# reversed.net
KiCad netlist of a schematic drawn in EAGLE
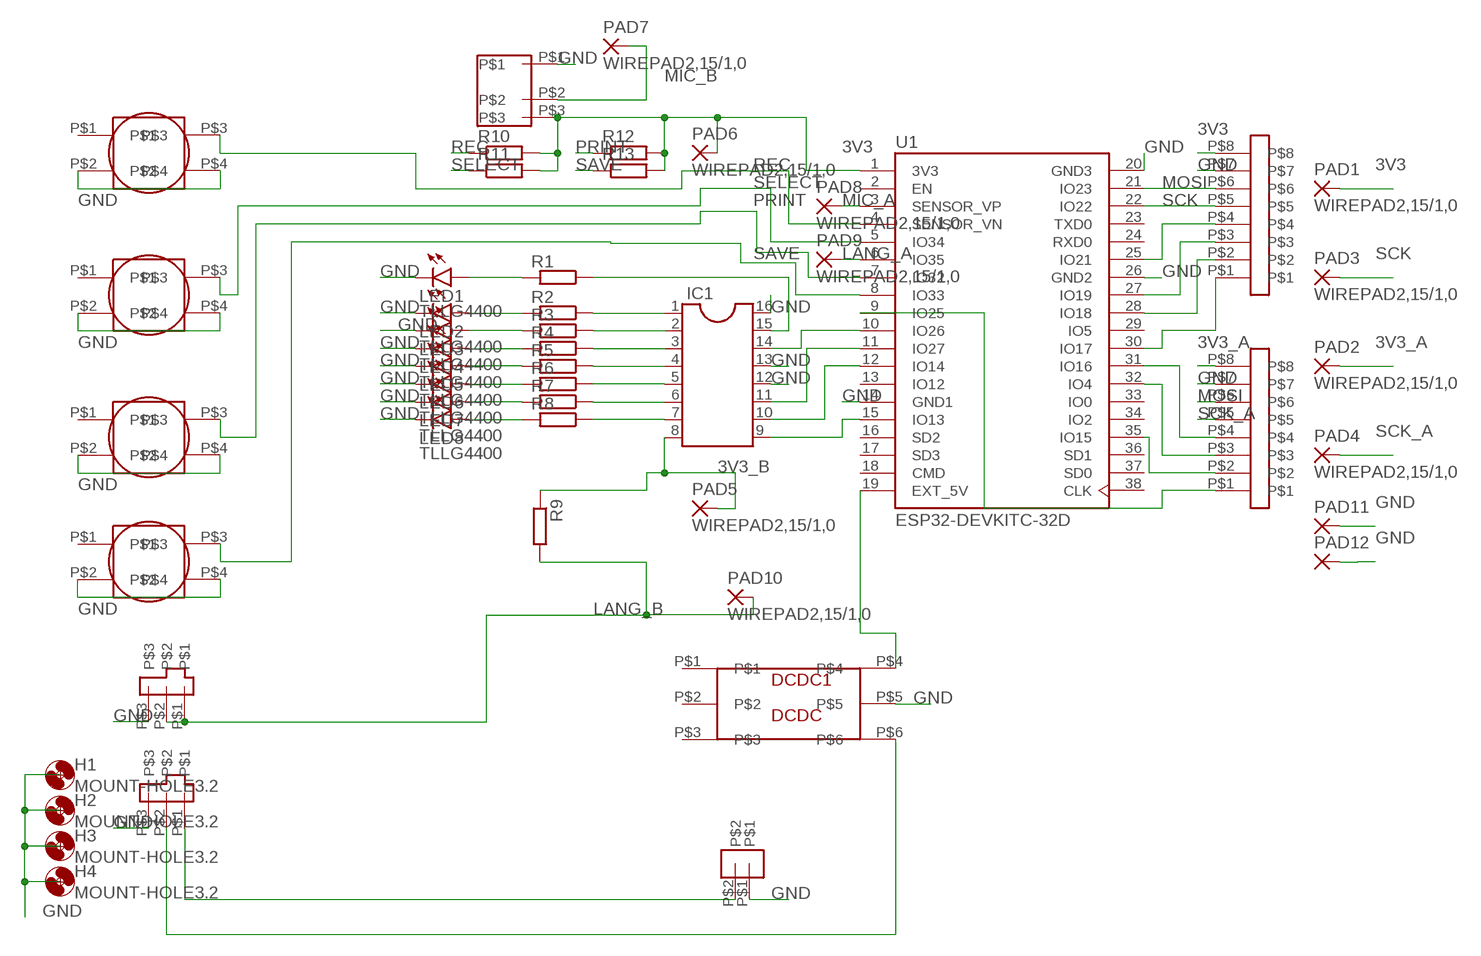
[diagram p0: schematic, sheet 1]

(export (version "E")
  (design (tool "Eeschema 10.0.6"))
  (components
    (comp (ref "BATTERY1")
      (value "BATTERY")
      (footprint "eagle-import:BATTERY")
      (libsource (lib "eagle-import") (part "BATTERY"))
    )
    (comp (ref "DCDC1")
      (value "DCDC")
      (footprint "eagle-import:DCDC")
      (libsource (lib "eagle-import") (part "DCDC"))
    )
    (comp (ref "DISPLAY1")
      (value "DISPLAY")
      (footprint "eagle-import:DISPLAY")
      (libsource (lib "eagle-import") (part "DISPLAY"))
    )
    (comp (ref "DISPLAY2")
      (value "DISPLAY")
      (footprint "eagle-import:DISPLAY")
      (libsource (lib "eagle-import") (part "DISPLAY"))
    )
    (comp (ref "H1")
      (value "MOUNT-HOLE3.2")
      (footprint "eagle-import:3,2")
      (libsource (lib "eagle-import") (part "MOUNT-HOLE3.2"))
    )
    (comp (ref "H2")
      (value "MOUNT-HOLE3.2")
      (footprint "eagle-import:3,2")
      (libsource (lib "eagle-import") (part "MOUNT-HOLE3.2"))
    )
    (comp (ref "H3")
      (value "MOUNT-HOLE3.2")
      (footprint "eagle-import:3,2")
      (libsource (lib "eagle-import") (part "MOUNT-HOLE3.2"))
    )
    (comp (ref "H4")
      (value "MOUNT-HOLE3.2")
      (footprint "eagle-import:3,2")
      (libsource (lib "eagle-import") (part "MOUNT-HOLE3.2"))
    )
    (comp (ref "IC1")
      (value "DIL16S")
      (footprint "eagle-import:SOCKET-16")
      (libsource (lib "eagle-import") (part "DIL16S"))
    )
    (comp (ref "LED1")
      (value "TLLG4400")
      (footprint "eagle-import:LED3MM")
      (fields (field (name "MF") "VISHAY SEMICONDUCTOR"))
      (libsource (lib "eagle-import") (part "TLLG4400"))
    )
    (comp (ref "LED2")
      (value "TLLG4400")
      (footprint "eagle-import:LED3MM")
      (fields (field (name "MF") "VISHAY SEMICONDUCTOR"))
      (libsource (lib "eagle-import") (part "TLLG4400"))
    )
    (comp (ref "LED3")
      (value "TLLG4400")
      (footprint "eagle-import:LED3MM")
      (fields (field (name "MF") "VISHAY SEMICONDUCTOR"))
      (libsource (lib "eagle-import") (part "TLLG4400"))
    )
    (comp (ref "LED4")
      (value "TLLG4400")
      (footprint "eagle-import:LED3MM")
      (fields (field (name "MF") "VISHAY SEMICONDUCTOR"))
      (libsource (lib "eagle-import") (part "TLLG4400"))
    )
    (comp (ref "LED5")
      (value "TLLG4400")
      (footprint "eagle-import:LED3MM")
      (fields (field (name "MF") "VISHAY SEMICONDUCTOR"))
      (libsource (lib "eagle-import") (part "TLLG4400"))
    )
    (comp (ref "LED6")
      (value "TLLG4400")
      (footprint "eagle-import:LED3MM")
      (fields (field (name "MF") "VISHAY SEMICONDUCTOR"))
      (libsource (lib "eagle-import") (part "TLLG4400"))
    )
    (comp (ref "LED7")
      (value "TLLG4400")
      (footprint "eagle-import:LED3MM")
      (fields (field (name "MF") "VISHAY SEMICONDUCTOR"))
      (libsource (lib "eagle-import") (part "TLLG4400"))
    )
    (comp (ref "LED8")
      (value "TLLG4400")
      (footprint "eagle-import:LED3MM")
      (fields (field (name "MF") "VISHAY SEMICONDUCTOR"))
      (libsource (lib "eagle-import") (part "TLLG4400"))
    )
    (comp (ref "MIC1")
      (value "MIC")
      (footprint "eagle-import:MIC")
      (libsource (lib "eagle-import") (part "MIC"))
    )
    (comp (ref "PAD1")
      (value "WIREPAD2,15/1,0")
      (footprint "eagle-import:2,15_1,0")
      (libsource (lib "eagle-import") (part "WIREPAD2,15/1,0"))
    )
    (comp (ref "PAD2")
      (value "WIREPAD2,15/1,0")
      (footprint "eagle-import:2,15_1,0")
      (libsource (lib "eagle-import") (part "WIREPAD2,15/1,0"))
    )
    (comp (ref "PAD3")
      (value "WIREPAD2,15/1,0")
      (footprint "eagle-import:2,15_1,0")
      (libsource (lib "eagle-import") (part "WIREPAD2,15/1,0"))
    )
    (comp (ref "PAD4")
      (value "WIREPAD2,15/1,0")
      (footprint "eagle-import:2,15_1,0")
      (libsource (lib "eagle-import") (part "WIREPAD2,15/1,0"))
    )
    (comp (ref "PAD5")
      (value "WIREPAD2,15/1,0")
      (footprint "eagle-import:2,15_1,0")
      (libsource (lib "eagle-import") (part "WIREPAD2,15/1,0"))
    )
    (comp (ref "PAD6")
      (value "WIREPAD2,15/1,0")
      (footprint "eagle-import:2,15_1,0")
      (libsource (lib "eagle-import") (part "WIREPAD2,15/1,0"))
    )
    (comp (ref "PAD7")
      (value "WIREPAD2,15/1,0")
      (footprint "eagle-import:2,15_1,0")
      (libsource (lib "eagle-import") (part "WIREPAD2,15/1,0"))
    )
    (comp (ref "PAD8")
      (value "WIREPAD2,15/1,0")
      (footprint "eagle-import:2,15_1,0")
      (libsource (lib "eagle-import") (part "WIREPAD2,15/1,0"))
    )
    (comp (ref "PAD9")
      (value "WIREPAD2,15/1,0")
      (footprint "eagle-import:2,15_1,0")
      (libsource (lib "eagle-import") (part "WIREPAD2,15/1,0"))
    )
    (comp (ref "PAD10")
      (value "WIREPAD2,15/1,0")
      (footprint "eagle-import:2,15_1,0")
      (libsource (lib "eagle-import") (part "WIREPAD2,15/1,0"))
    )
    (comp (ref "PAD11")
      (value "2,15/1,0")
      (footprint "eagle-import:2,15_1,0")
      (libsource (lib "eagle-import") (part "2,15/1,0"))
    )
    (comp (ref "PAD12")
      (value "2,15/1,0")
      (footprint "eagle-import:2,15_1,0")
      (libsource (lib "eagle-import") (part "2,15/1,0"))
    )
    (comp (ref "R1")
      (value "SMK")
      (footprint "eagle-import:SMK")
      (libsource (lib "eagle-import") (part "SMK"))
    )
    (comp (ref "R2")
      (value "SMK")
      (footprint "eagle-import:SMK")
      (libsource (lib "eagle-import") (part "SMK"))
    )
    (comp (ref "R3")
      (value "SMK")
      (footprint "eagle-import:SMK")
      (libsource (lib "eagle-import") (part "SMK"))
    )
    (comp (ref "R4")
      (value "SMK")
      (footprint "eagle-import:SMK")
      (libsource (lib "eagle-import") (part "SMK"))
    )
    (comp (ref "R5")
      (value "SMK")
      (footprint "eagle-import:SMK")
      (libsource (lib "eagle-import") (part "SMK"))
    )
    (comp (ref "R6")
      (value "SMK")
      (footprint "eagle-import:SMK")
      (libsource (lib "eagle-import") (part "SMK"))
    )
    (comp (ref "R7")
      (value "SMK")
      (footprint "eagle-import:SMK")
      (libsource (lib "eagle-import") (part "SMK"))
    )
    (comp (ref "R8")
      (value "SMK")
      (footprint "eagle-import:SMK")
      (libsource (lib "eagle-import") (part "SMK"))
    )
    (comp (ref "R9")
      (value "R-EU_0207/10")
      (footprint "eagle-import:0207_10")
      (libsource (lib "eagle-import") (part "R-EU_0207/10"))
    )
    (comp (ref "R10")
      (value "R-EU_0207/10")
      (footprint "eagle-import:0207_10")
      (libsource (lib "eagle-import") (part "R-EU_0207/10"))
    )
    (comp (ref "R11")
      (value "R-EU_0207/10")
      (footprint "eagle-import:0207_10")
      (libsource (lib "eagle-import") (part "R-EU_0207/10"))
    )
    (comp (ref "R12")
      (value "R-EU_0207/10")
      (footprint "eagle-import:0207_10")
      (libsource (lib "eagle-import") (part "R-EU_0207/10"))
    )
    (comp (ref "R13")
      (value "R-EU_0207/10")
      (footprint "eagle-import:0207_10")
      (libsource (lib "eagle-import") (part "R-EU_0207/10"))
    )
    (comp (ref "SWITCH1")
      (value "SWITCH")
      (footprint "eagle-import:SWITCH")
      (libsource (lib "eagle-import") (part "SWITCH"))
    )
    (comp (ref "SWITCH2")
      (value "SWITCH")
      (footprint "eagle-import:SWITCH")
      (libsource (lib "eagle-import") (part "SWITCH"))
    )
    (comp (ref "SWITCH3")
      (value "SWITCH")
      (footprint "eagle-import:SWITCH")
      (libsource (lib "eagle-import") (part "SWITCH"))
    )
    (comp (ref "SWITCH4")
      (value "SWITCH")
      (footprint "eagle-import:SWITCH")
      (libsource (lib "eagle-import") (part "SWITCH"))
    )
    (comp (ref "TOGGLE1")
      (value "TOGGLE")
      (footprint "eagle-import:TOGGLE")
      (libsource (lib "eagle-import") (part "TOGGLE"))
    )
    (comp (ref "TOGGLE2")
      (value "TOGGLE")
      (footprint "eagle-import:TOGGLE")
      (libsource (lib "eagle-import") (part "TOGGLE"))
    )
    (comp (ref "U1")
      (value "ESP32-DEVKITC-32D")
      (footprint "eagle-import:MODULE_ESP32-DEVKITC-32D")
      (fields (field (name "MF") "Espressif Systems"))
      (libsource (lib "eagle-import") (part "ESP32-DEVKITC-32D"))
    )
  )
  (nets
    (net (code "1") (name "/3V3") (class "Default")
      (node (ref "DISPLAY1") (pin "P$8") (pinfunction "P$8_P$8") (pintype "bidirectional"))
      (node (ref "MIC1") (pin "P$3") (pinfunction "P$3_P$3") (pintype "bidirectional"))
      (node (ref "PAD1") (pin "1") (pinfunction "P_1") (pintype "passive"))
      (node (ref "PAD6") (pin "1") (pinfunction "P_1") (pintype "passive"))
      (node (ref "R10") (pin "2") (pinfunction "2_2") (pintype "passive"))
      (node (ref "R11") (pin "2") (pinfunction "2_2") (pintype "passive"))
      (node (ref "R12") (pin "2") (pinfunction "2_2") (pintype "passive"))
      (node (ref "R13") (pin "2") (pinfunction "2_2") (pintype "passive"))
      (node (ref "U1") (pin "1") (pinfunction "3V3_1") (pintype "power_in"))
    )
    (net (code "2") (name "/3V3_A") (class "Default")
      (node (ref "DISPLAY2") (pin "P$8") (pinfunction "P$8_P$8") (pintype "bidirectional"))
      (node (ref "PAD2") (pin "1") (pinfunction "P_1") (pintype "passive"))
    )
    (net (code "3") (name "/3V3_B") (class "Default")
      (node (ref "IC1") (pin "8") (pinfunction "8_8") (pintype "passive"))
      (node (ref "PAD5") (pin "1") (pinfunction "P_1") (pintype "passive"))
      (node (ref "R9") (pin "1") (pinfunction "1_1") (pintype "passive"))
    )
    (net (code "4") (name "/GND") (class "Default")
      (node (ref "BATTERY1") (pin "P$1") (pinfunction "P$1_P$1") (pintype "bidirectional"))
      (node (ref "DCDC1") (pin "P$5") (pinfunction "P$5_P$5") (pintype "bidirectional"))
      (node (ref "DISPLAY1") (pin "P$7") (pinfunction "P$7_P$7") (pintype "bidirectional"))
      (node (ref "DISPLAY2") (pin "P$7") (pinfunction "P$7_P$7") (pintype "bidirectional"))
      (node (ref "IC1") (pin "12") (pinfunction "12_12") (pintype "passive"))
      (node (ref "IC1") (pin "13") (pinfunction "13_13") (pintype "passive"))
      (node (ref "IC1") (pin "16") (pinfunction "16_16") (pintype "passive"))
      (node (ref "LED1") (pin "K") (pinfunction "C_K") (pintype "passive"))
      (node (ref "LED2") (pin "K") (pinfunction "C_K") (pintype "passive"))
      (node (ref "LED3") (pin "K") (pinfunction "C_K") (pintype "passive"))
      (node (ref "LED4") (pin "K") (pinfunction "C_K") (pintype "passive"))
      (node (ref "LED5") (pin "K") (pinfunction "C_K") (pintype "passive"))
      (node (ref "LED6") (pin "K") (pinfunction "C_K") (pintype "passive"))
      (node (ref "LED7") (pin "K") (pinfunction "C_K") (pintype "passive"))
      (node (ref "LED8") (pin "K") (pinfunction "C_K") (pintype "passive"))
      (node (ref "MIC1") (pin "P$1") (pinfunction "P$1_P$1") (pintype "bidirectional"))
      (node (ref "PAD11") (pin "1") (pinfunction "P_1") (pintype "passive"))
      (node (ref "PAD12") (pin "1") (pinfunction "P_1") (pintype "passive"))
      (node (ref "SWITCH1") (pin "P$2") (pinfunction "P$2_P$2") (pintype "bidirectional"))
      (node (ref "SWITCH1") (pin "P$4") (pinfunction "P$4_P$4") (pintype "bidirectional"))
      (node (ref "SWITCH2") (pin "P$2") (pinfunction "P$2_P$2") (pintype "bidirectional"))
      (node (ref "SWITCH2") (pin "P$4") (pinfunction "P$4_P$4") (pintype "bidirectional"))
      (node (ref "SWITCH3") (pin "P$2") (pinfunction "P$2_P$2") (pintype "bidirectional"))
      (node (ref "SWITCH3") (pin "P$4") (pinfunction "P$4_P$4") (pintype "bidirectional"))
      (node (ref "SWITCH4") (pin "P$2") (pinfunction "P$2_P$2") (pintype "bidirectional"))
      (node (ref "SWITCH4") (pin "P$4") (pinfunction "P$4_P$4") (pintype "bidirectional"))
      (node (ref "TOGGLE1") (pin "P$3") (pinfunction "P$3_P$3") (pintype "bidirectional"))
      (node (ref "TOGGLE2") (pin "P$3") (pinfunction "P$3_P$3") (pintype "bidirectional"))
      (node (ref "U1") (pin "14") (pinfunction "GND1_14") (pintype "power_in"))
      (node (ref "U1") (pin "20") (pinfunction "GND3_20") (pintype "power_in"))
      (node (ref "U1") (pin "26") (pinfunction "GND2_26") (pintype "power_in"))
    )
    (net (code "5") (name "/LANG_A") (class "Default")
      (node (ref "PAD9") (pin "1") (pinfunction "P_1") (pintype "passive"))
      (node (ref "U1") (pin "6") (pinfunction "IO35_6") (pintype "bidirectional"))
    )
    (net (code "6") (name "/LANG_B") (class "Default")
      (node (ref "PAD10") (pin "1") (pinfunction "P_1") (pintype "passive"))
      (node (ref "R9") (pin "2") (pinfunction "2_2") (pintype "passive"))
      (node (ref "TOGGLE1") (pin "P$1") (pinfunction "P$1_P$1") (pintype "bidirectional"))
      (node (ref "TOGGLE1") (pin "P$2") (pinfunction "P$2_P$2") (pintype "bidirectional"))
    )
    (net (code "7") (name "/MIC_A") (class "Default")
      (node (ref "PAD8") (pin "1") (pinfunction "P_1") (pintype "passive"))
      (node (ref "U1") (pin "3") (pinfunction "SENSOR_VP_3") (pintype "input"))
    )
    (net (code "8") (name "/MIC_B") (class "Default")
      (node (ref "MIC1") (pin "P$2") (pinfunction "P$2_P$2") (pintype "bidirectional"))
      (node (ref "PAD7") (pin "1") (pinfunction "P_1") (pintype "passive"))
    )
    (net (code "9") (name "/MOSI") (class "Default")
      (node (ref "DISPLAY1") (pin "P$6") (pinfunction "P$6_P$6") (pintype "bidirectional"))
      (node (ref "DISPLAY2") (pin "P$6") (pinfunction "P$6_P$6") (pintype "bidirectional"))
      (node (ref "U1") (pin "21") (pinfunction "IO23_21") (pintype "bidirectional"))
    )
    (net (code "10") (name "/PRINT") (class "Default")
      (node (ref "R12") (pin "1") (pinfunction "1_1") (pintype "passive"))
      (node (ref "SWITCH3") (pin "P$3") (pinfunction "P$3_P$3") (pintype "bidirectional"))
      (node (ref "U1") (pin "7") (pinfunction "IO32_7") (pintype "bidirectional"))
    )
    (net (code "11") (name "/REC") (class "Default")
      (node (ref "R10") (pin "1") (pinfunction "1_1") (pintype "passive"))
      (node (ref "SWITCH1") (pin "P$3") (pinfunction "P$3_P$3") (pintype "bidirectional"))
      (node (ref "U1") (pin "4") (pinfunction "SENSOR_VN_4") (pintype "input"))
    )
    (net (code "12") (name "/SAVE") (class "Default")
      (node (ref "R13") (pin "1") (pinfunction "1_1") (pintype "passive"))
      (node (ref "SWITCH4") (pin "P$3") (pinfunction "P$3_P$3") (pintype "bidirectional"))
      (node (ref "U1") (pin "8") (pinfunction "IO33_8") (pintype "bidirectional"))
    )
    (net (code "13") (name "/SCK") (class "Default")
      (node (ref "DISPLAY1") (pin "P$5") (pinfunction "P$5_P$5") (pintype "bidirectional"))
      (node (ref "PAD3") (pin "1") (pinfunction "P_1") (pintype "passive"))
      (node (ref "U1") (pin "22") (pinfunction "IO22_22") (pintype "bidirectional"))
    )
    (net (code "14") (name "/SCK_A") (class "Default")
      (node (ref "DISPLAY2") (pin "P$5") (pinfunction "P$5_P$5") (pintype "bidirectional"))
      (node (ref "PAD4") (pin "1") (pinfunction "P_1") (pintype "passive"))
    )
    (net (code "15") (name "/SELECT") (class "Default")
      (node (ref "R11") (pin "1") (pinfunction "1_1") (pintype "passive"))
      (node (ref "SWITCH2") (pin "P$3") (pinfunction "P$3_P$3") (pintype "bidirectional"))
      (node (ref "U1") (pin "5") (pinfunction "IO34_5") (pintype "bidirectional"))
    )
    (net (code "16") (name "Net-(BATTERY1-PadP$2)") (class "Default")
      (node (ref "BATTERY1") (pin "P$2") (pinfunction "P$2_P$2") (pintype "bidirectional"))
      (node (ref "TOGGLE2") (pin "P$1") (pinfunction "P$1_P$1") (pintype "bidirectional"))
    )
    (net (code "17") (name "Net-(DCDC1-PadP$6)") (class "Default")
      (node (ref "DCDC1") (pin "P$6") (pinfunction "P$6_P$6") (pintype "bidirectional"))
      (node (ref "TOGGLE2") (pin "P$2") (pinfunction "P$2_P$2") (pintype "bidirectional"))
    )
    (net (code "18") (name "Net-(IC1-Pad1)") (class "Default")
      (node (ref "IC1") (pin "1") (pinfunction "1_1") (pintype "passive"))
      (node (ref "R2") (pin "1") (pinfunction "1_1") (pintype "passive"))
    )
    (net (code "19") (name "Net-(IC1-Pad2)") (class "Default")
      (node (ref "IC1") (pin "2") (pinfunction "2_2") (pintype "passive"))
      (node (ref "R3") (pin "1") (pinfunction "1_1") (pintype "passive"))
    )
    (net (code "20") (name "Net-(IC1-Pad3)") (class "Default")
      (node (ref "IC1") (pin "3") (pinfunction "3_3") (pintype "passive"))
      (node (ref "R4") (pin "1") (pinfunction "1_1") (pintype "passive"))
    )
    (net (code "21") (name "Net-(IC1-Pad4)") (class "Default")
      (node (ref "IC1") (pin "4") (pinfunction "4_4") (pintype "passive"))
      (node (ref "R5") (pin "1") (pinfunction "1_1") (pintype "passive"))
    )
    (net (code "22") (name "Net-(IC1-Pad5)") (class "Default")
      (node (ref "IC1") (pin "5") (pinfunction "5_5") (pintype "passive"))
      (node (ref "R6") (pin "1") (pinfunction "1_1") (pintype "passive"))
    )
    (net (code "23") (name "Net-(IC1-Pad6)") (class "Default")
      (node (ref "IC1") (pin "6") (pinfunction "6_6") (pintype "passive"))
      (node (ref "R7") (pin "1") (pinfunction "1_1") (pintype "passive"))
    )
    (net (code "24") (name "Net-(IC1-Pad7)") (class "Default")
      (node (ref "IC1") (pin "7") (pinfunction "7_7") (pintype "passive"))
      (node (ref "R8") (pin "1") (pinfunction "1_1") (pintype "passive"))
    )
    (net (code "25") (name "Net-(IC1-Pad15)") (class "Default")
      (node (ref "IC1") (pin "15") (pinfunction "15_15") (pintype "passive"))
      (node (ref "R1") (pin "1") (pinfunction "1_1") (pintype "passive"))
    )
    (net (code "26") (name "Net-(LED1-PadA)") (class "Default")
      (node (ref "LED1") (pin "A") (pinfunction "A_A") (pintype "passive"))
      (node (ref "R1") (pin "2") (pinfunction "2_2") (pintype "passive"))
    )
    (net (code "27") (name "Net-(LED2-PadA)") (class "Default")
      (node (ref "LED2") (pin "A") (pinfunction "A_A") (pintype "passive"))
      (node (ref "R2") (pin "2") (pinfunction "2_2") (pintype "passive"))
    )
    (net (code "28") (name "Net-(LED3-PadA)") (class "Default")
      (node (ref "LED3") (pin "A") (pinfunction "A_A") (pintype "passive"))
      (node (ref "R3") (pin "2") (pinfunction "2_2") (pintype "passive"))
    )
    (net (code "29") (name "Net-(LED4-PadA)") (class "Default")
      (node (ref "LED4") (pin "A") (pinfunction "A_A") (pintype "passive"))
      (node (ref "R4") (pin "2") (pinfunction "2_2") (pintype "passive"))
    )
    (net (code "30") (name "Net-(LED5-PadA)") (class "Default")
      (node (ref "LED5") (pin "A") (pinfunction "A_A") (pintype "passive"))
      (node (ref "R5") (pin "2") (pinfunction "2_2") (pintype "passive"))
    )
    (net (code "31") (name "Net-(LED6-PadA)") (class "Default")
      (node (ref "LED6") (pin "A") (pinfunction "A_A") (pintype "passive"))
      (node (ref "R6") (pin "2") (pinfunction "2_2") (pintype "passive"))
    )
    (net (code "32") (name "Net-(LED7-PadA)") (class "Default")
      (node (ref "LED7") (pin "A") (pinfunction "A_A") (pintype "passive"))
      (node (ref "R7") (pin "2") (pinfunction "2_2") (pintype "passive"))
    )
    (net (code "33") (name "Net-(LED8-PadA)") (class "Default")
      (node (ref "LED8") (pin "A") (pinfunction "A_A") (pintype "passive"))
      (node (ref "R8") (pin "2") (pinfunction "2_2") (pintype "passive"))
    )
    (net (code "34") (name "Net-(U1-EXT_5V)") (class "Default")
      (node (ref "DCDC1") (pin "P$4") (pinfunction "P$4_P$4") (pintype "bidirectional"))
      (node (ref "U1") (pin "19") (pinfunction "EXT_5V_19") (pintype "power_in"))
    )
    (net (code "35") (name "Net-(U1-IO4)") (class "Default")
      (node (ref "DISPLAY2") (pin "P$3") (pinfunction "P$3_P$3") (pintype "bidirectional"))
      (node (ref "U1") (pin "32") (pinfunction "IO4_32") (pintype "bidirectional"))
    )
    (net (code "36") (name "Net-(U1-IO13)") (class "Default")
      (node (ref "IC1") (pin "9") (pinfunction "9_9") (pintype "passive"))
      (node (ref "U1") (pin "15") (pinfunction "IO13_15") (pintype "bidirectional"))
    )
    (net (code "37") (name "Net-(U1-IO14)") (class "Default")
      (node (ref "IC1") (pin "10") (pinfunction "10_10") (pintype "passive"))
      (node (ref "U1") (pin "12") (pinfunction "IO14_12") (pintype "bidirectional"))
    )
    (net (code "38") (name "Net-(U1-IO15)") (class "Default")
      (node (ref "DISPLAY2") (pin "P$2") (pinfunction "P$2_P$2") (pintype "bidirectional"))
      (node (ref "U1") (pin "35") (pinfunction "IO15_35") (pintype "bidirectional"))
    )
    (net (code "39") (name "Net-(U1-IO16)") (class "Default")
      (node (ref "DISPLAY2") (pin "P$4") (pinfunction "P$4_P$4") (pintype "bidirectional"))
      (node (ref "U1") (pin "31") (pinfunction "IO16_31") (pintype "bidirectional"))
    )
    (net (code "40") (name "Net-(U1-IO17)") (class "Default")
      (node (ref "DISPLAY1") (pin "P$1") (pinfunction "P$1_P$1") (pintype "bidirectional"))
      (node (ref "U1") (pin "30") (pinfunction "IO17_30") (pintype "bidirectional"))
    )
    (net (code "41") (name "Net-(U1-IO18)") (class "Default")
      (node (ref "DISPLAY1") (pin "P$2") (pinfunction "P$2_P$2") (pintype "bidirectional"))
      (node (ref "U1") (pin "28") (pinfunction "IO18_28") (pintype "bidirectional"))
    )
    (net (code "42") (name "Net-(U1-IO19)") (class "Default")
      (node (ref "DISPLAY1") (pin "P$3") (pinfunction "P$3_P$3") (pintype "bidirectional"))
      (node (ref "U1") (pin "27") (pinfunction "IO19_27") (pintype "bidirectional"))
    )
    (net (code "43") (name "Net-(U1-IO21)") (class "Default")
      (node (ref "DISPLAY1") (pin "P$4") (pinfunction "P$4_P$4") (pintype "bidirectional"))
      (node (ref "U1") (pin "25") (pinfunction "IO21_25") (pintype "bidirectional"))
    )
    (net (code "44") (name "Net-(U1-IO25)") (class "Default")
      (node (ref "DISPLAY2") (pin "P$1") (pinfunction "P$1_P$1") (pintype "bidirectional"))
      (node (ref "U1") (pin "9") (pinfunction "IO25_9") (pintype "bidirectional"))
    )
    (net (code "45") (name "Net-(U1-IO26)") (class "Default")
      (node (ref "IC1") (pin "14") (pinfunction "14_14") (pintype "passive"))
      (node (ref "U1") (pin "10") (pinfunction "IO26_10") (pintype "bidirectional"))
    )
    (net (code "46") (name "Net-(U1-IO27)") (class "Default")
      (node (ref "IC1") (pin "11") (pinfunction "11_11") (pintype "passive"))
      (node (ref "U1") (pin "11") (pinfunction "IO27_11") (pintype "bidirectional"))
    )
    (net (code "47") (name "unconnected-(DCDC1-PadP$1)") (class "Default")
      (node (ref "DCDC1") (pin "P$1") (pinfunction "P$1_P$1") (pintype "bidirectional"))
    )
    (net (code "48") (name "unconnected-(DCDC1-PadP$2)") (class "Default")
      (node (ref "DCDC1") (pin "P$2") (pinfunction "P$2_P$2") (pintype "bidirectional"))
    )
    (net (code "49") (name "unconnected-(DCDC1-PadP$3)") (class "Default")
      (node (ref "DCDC1") (pin "P$3") (pinfunction "P$3_P$3") (pintype "bidirectional"))
    )
    (net (code "50") (name "unconnected-(SWITCH1-PadP$1)") (class "Default")
      (node (ref "SWITCH1") (pin "P$1") (pinfunction "P$1_P$1") (pintype "bidirectional"))
    )
    (net (code "51") (name "unconnected-(SWITCH2-PadP$1)") (class "Default")
      (node (ref "SWITCH2") (pin "P$1") (pinfunction "P$1_P$1") (pintype "bidirectional"))
    )
    (net (code "52") (name "unconnected-(SWITCH3-PadP$1)") (class "Default")
      (node (ref "SWITCH3") (pin "P$1") (pinfunction "P$1_P$1") (pintype "bidirectional"))
    )
    (net (code "53") (name "unconnected-(SWITCH4-PadP$1)") (class "Default")
      (node (ref "SWITCH4") (pin "P$1") (pinfunction "P$1_P$1") (pintype "bidirectional"))
    )
    (net (code "54") (name "unconnected-(U1-CLK-Pad38)") (class "Default")
      (node (ref "U1") (pin "38") (pinfunction "CLK_38") (pintype "input"))
    )
    (net (code "55") (name "unconnected-(U1-CMD-Pad18)") (class "Default")
      (node (ref "U1") (pin "18") (pinfunction "CMD_18") (pintype "bidirectional"))
    )
    (net (code "56") (name "unconnected-(U1-EN-Pad2)") (class "Default")
      (node (ref "U1") (pin "2") (pinfunction "EN_2") (pintype "input"))
    )
    (net (code "57") (name "unconnected-(U1-IO0-Pad33)") (class "Default")
      (node (ref "U1") (pin "33") (pinfunction "IO0_33") (pintype "bidirectional"))
    )
    (net (code "58") (name "unconnected-(U1-IO2-Pad34)") (class "Default")
      (node (ref "U1") (pin "34") (pinfunction "IO2_34") (pintype "bidirectional"))
    )
    (net (code "59") (name "unconnected-(U1-IO5-Pad29)") (class "Default")
      (node (ref "U1") (pin "29") (pinfunction "IO5_29") (pintype "bidirectional"))
    )
    (net (code "60") (name "unconnected-(U1-IO12-Pad13)") (class "Default")
      (node (ref "U1") (pin "13") (pinfunction "IO12_13") (pintype "bidirectional"))
    )
    (net (code "61") (name "unconnected-(U1-RXD0-Pad24)") (class "Default")
      (node (ref "U1") (pin "24") (pinfunction "RXD0_24") (pintype "input"))
    )
    (net (code "62") (name "unconnected-(U1-SD0-Pad37)") (class "Default")
      (node (ref "U1") (pin "37") (pinfunction "SD0_37") (pintype "bidirectional"))
    )
    (net (code "63") (name "unconnected-(U1-SD1-Pad36)") (class "Default")
      (node (ref "U1") (pin "36") (pinfunction "SD1_36") (pintype "bidirectional"))
    )
    (net (code "64") (name "unconnected-(U1-SD2-Pad16)") (class "Default")
      (node (ref "U1") (pin "16") (pinfunction "SD2_16") (pintype "bidirectional"))
    )
    (net (code "65") (name "unconnected-(U1-SD3-Pad17)") (class "Default")
      (node (ref "U1") (pin "17") (pinfunction "SD3_17") (pintype "bidirectional"))
    )
    (net (code "66") (name "unconnected-(U1-TXD0-Pad23)") (class "Default")
      (node (ref "U1") (pin "23") (pinfunction "TXD0_23") (pintype "output"))
    )
  )
)
